# WiFi.net
KiCad netlist of a schematic drawn in Altium Designer
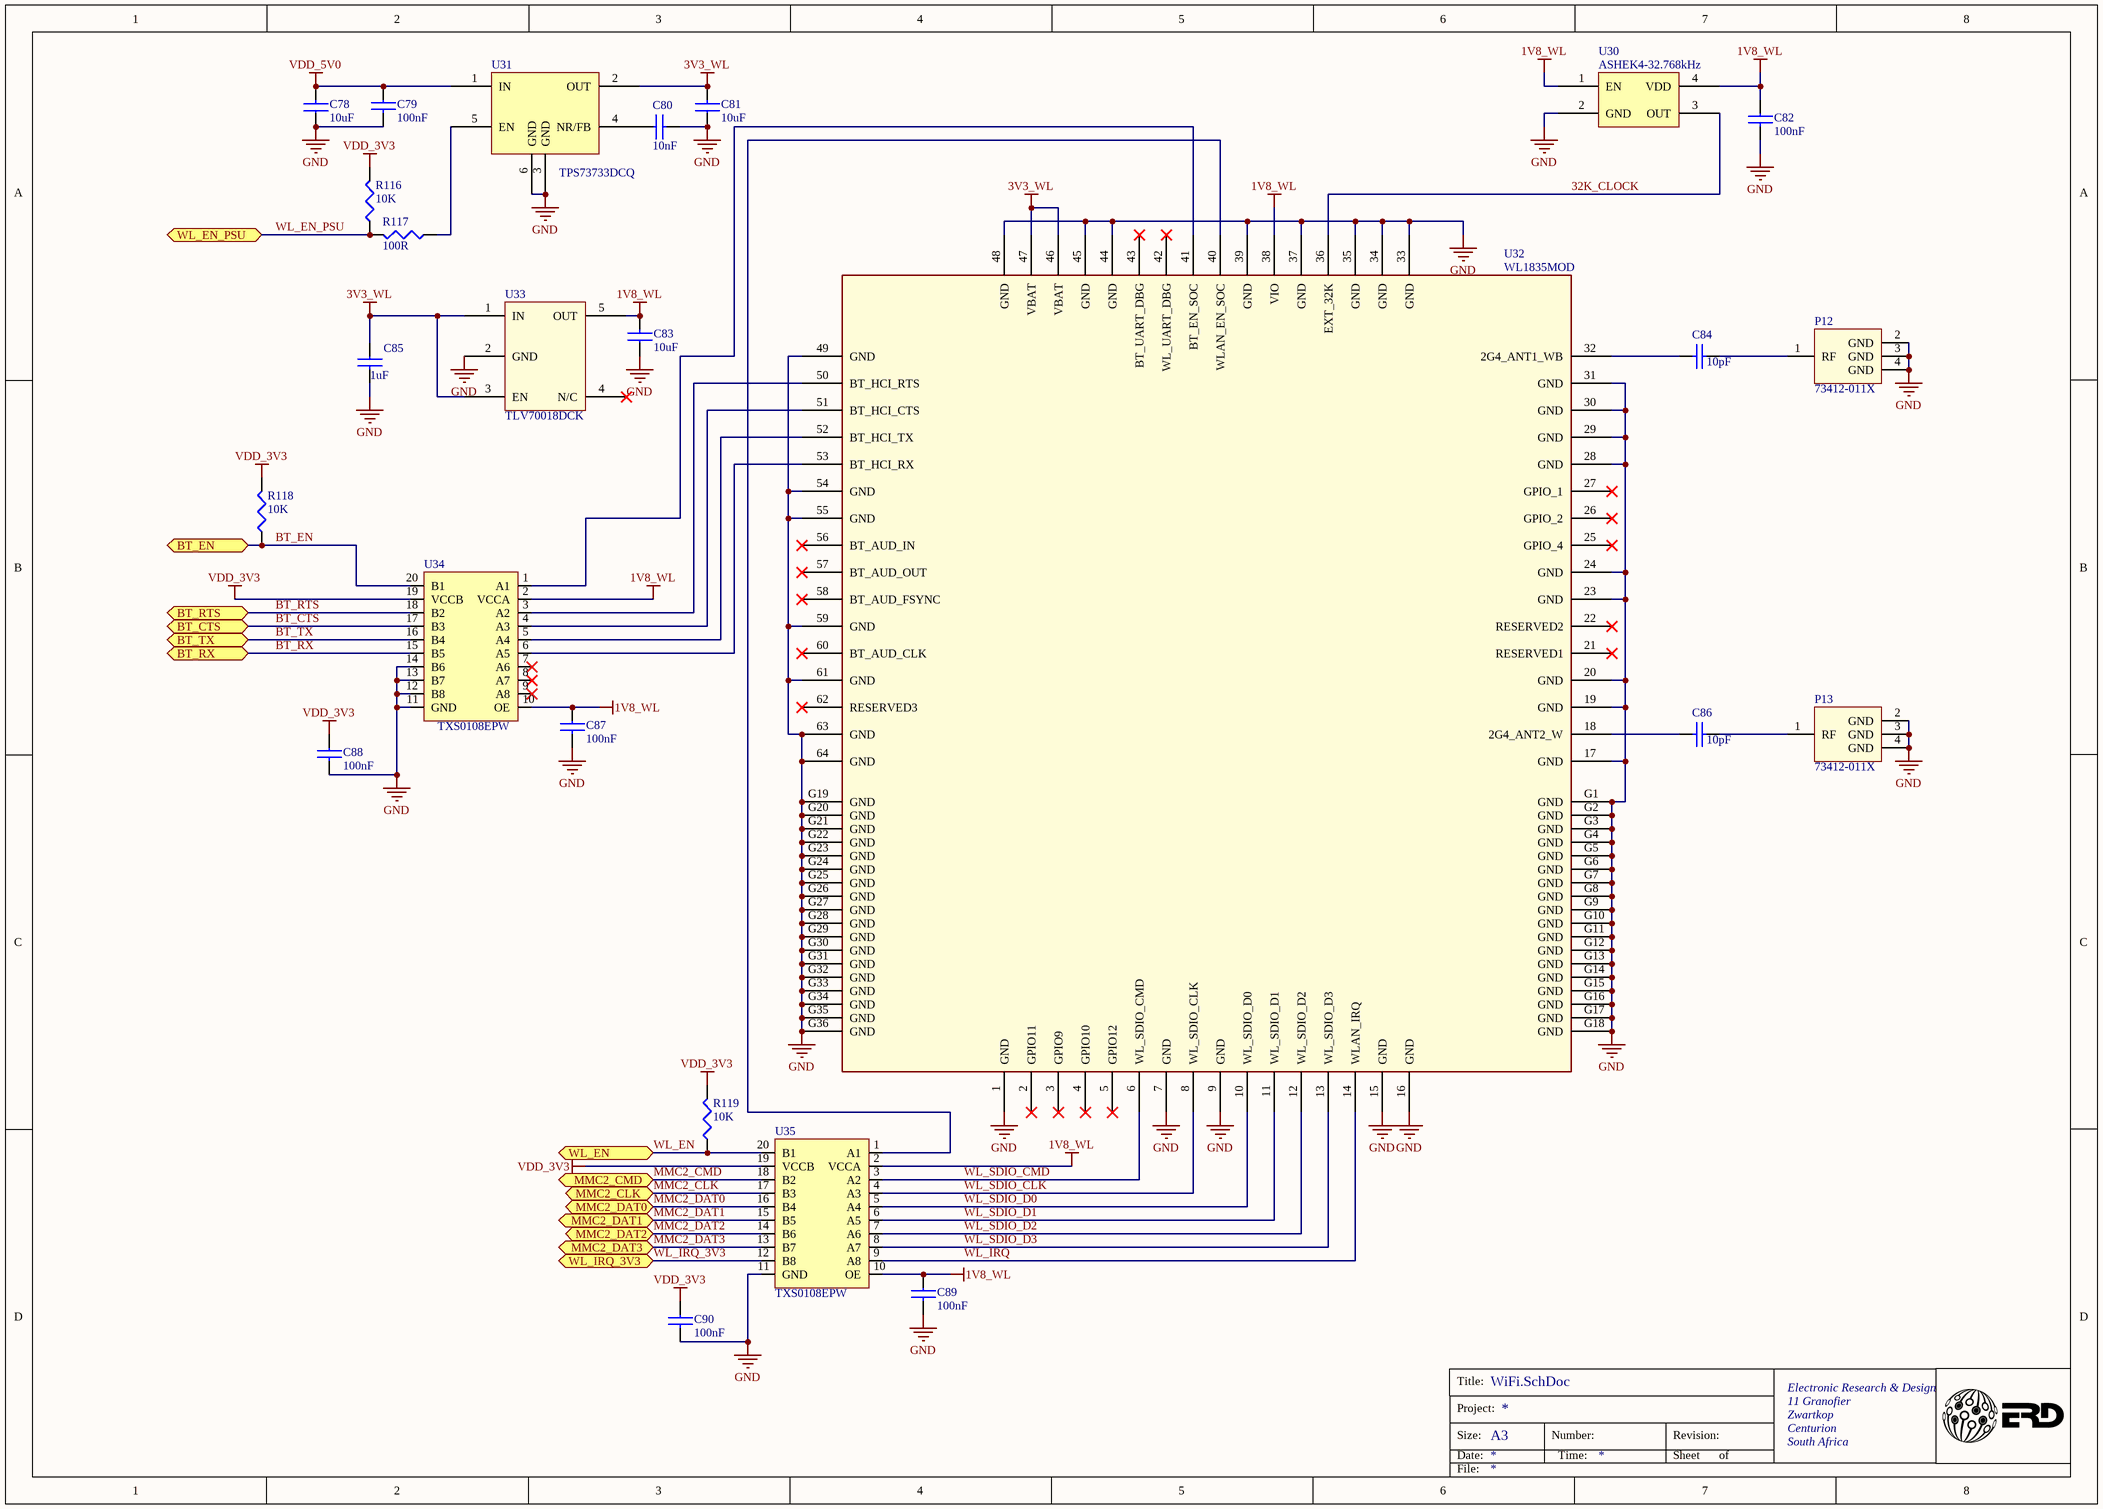
[diagram p0: WiFi.SchDoc]

(export (version "E")
  (design (tool "Eeschema 10.0.6"))
  (components
    (comp (ref "C78")
      (value "10uF")
      (footprint "CC0603")
      (description "CAP CER 10UF 25V 20% X5R 0603")
      (fields (field (name "MANUFACTURER") "Murata") (field (name "PARTNUMBER") "GRM188R61E106MA73D"))
      (libsource (lib "ERD TiAm") (part "CAP CER 0.1UF 10V 10% X5R 0402"))
    )
    (comp (ref "C79")
      (value "100nF")
      (footprint "CC0402")
      (description "CAP CER 0.1UF 50V 10% X7R 0402")
      (fields (field (name "MANUFACTURER") "Murata") (field (name "PARTNUMBER") "GCM155R71H104KE02D"))
      (libsource (lib "ERD TiAm") (part "CAP CER 0.1UF 10V 10% X5R 0402"))
    )
    (comp (ref "C80")
      (value "10nF")
      (footprint "CC0402")
      (description "CAP CER 10NF 50V 10% X7R 0402")
      (fields (field (name "MANUFACTURER") "Murata") (field (name "PART NUMBER") "GRM155R71H103KA88J"))
      (libsource (lib "ERD TiAm") (part "CAP CER 0.1UF 10V 10% X5R 0402"))
    )
    (comp (ref "C81")
      (value "10uF")
      (footprint "CC0603")
      (description "CAP CER 10UF 25V 20% X5R 0603")
      (fields (field (name "MANUFACTURER") "Murata") (field (name "PARTNUMBER") "GRM188R61E106MA73D"))
      (libsource (lib "ERD TiAm") (part "CAP CER 0.1UF 10V 10% X5R 0402"))
    )
    (comp (ref "C82")
      (value "100nF")
      (footprint "CC0402")
      (description "CAP CER 0.1UF 50V 10% X7R 0402")
      (fields (field (name "MANUFACTURER") "Murata") (field (name "PARTNUMBER") "GCM155R71H104KE02D"))
      (libsource (lib "ERD TiAm") (part "CAP CER 0.1UF 10V 10% X5R 0402"))
    )
    (comp (ref "C83")
      (value "10uF")
      (footprint "CC0603")
      (description "CAP CER 10UF 25V 20% X5R 0603")
      (fields (field (name "MANUFACTURER") "Murata") (field (name "PARTNUMBER") "GRM188R61E106MA73D"))
      (libsource (lib "ERD TiAm") (part "CAP CER 0.1UF 10V 10% X5R 0402"))
    )
    (comp (ref "C84")
      (value "10pF")
      (footprint "CC0402")
      (description "10pF/16V/X7R")
      (fields (field (name "TOLERANCE") "±20%") (field (name "VOLTAGE") "25V"))
      (libsource (lib "*") (part "CAPCERAMIC"))
    )
    (comp (ref "C85")
      (value "1uF")
      (footprint "CC0402")
      (description "CAP CER 1UF 10V 20% X5R 0402")
      (fields (field (name "MANUFACTURER") "Murata") (field (name "PART NUMBER") "GRM153R61A105ME95D"))
      (libsource (lib "ERD TiAm") (part "CAP CER 0.1UF 10V 10% X5R 0402"))
    )
    (comp (ref "C86")
      (value "10pF")
      (footprint "CC0402")
      (description "10pF/16V/X7R")
      (fields (field (name "TOLERANCE") "±20%") (field (name "VOLTAGE") "25V"))
      (libsource (lib "*") (part "CAPCERAMIC"))
    )
    (comp (ref "C87")
      (value "100nF")
      (footprint "CC0402")
      (description "CAP CER 0.1UF 50V 10% X7R 0402")
      (fields (field (name "MANUFACTURER") "Murata") (field (name "PARTNUMBER") "GCM155R71H104KE02D"))
      (libsource (lib "ERD TiAm") (part "CAP CER 0.1UF 10V 10% X5R 0402"))
    )
    (comp (ref "C88")
      (value "100nF")
      (footprint "CC0402")
      (description "CAP CER 0.1UF 50V 10% X7R 0402")
      (fields (field (name "MANUFACTURER") "Murata") (field (name "PARTNUMBER") "GCM155R71H104KE02D"))
      (libsource (lib "ERD TiAm") (part "CAP CER 0.1UF 10V 10% X5R 0402"))
    )
    (comp (ref "C89")
      (value "100nF")
      (footprint "CC0402")
      (description "CAP CER 0.1UF 50V 10% X7R 0402")
      (fields (field (name "MANUFACTURER") "Murata") (field (name "PARTNUMBER") "GCM155R71H104KE02D"))
      (libsource (lib "ERD TiAm") (part "CAP CER 0.1UF 10V 10% X5R 0402"))
    )
    (comp (ref "C90")
      (value "100nF")
      (footprint "CC0402")
      (description "CAP CER 0.1UF 50V 10% X7R 0402")
      (fields (field (name "MANUFACTURER") "Murata") (field (name "PARTNUMBER") "GCM155R71H104KE02D"))
      (libsource (lib "ERD TiAm") (part "CAP CER 0.1UF 10V 10% X5R 0402"))
    )
    (comp (ref "P12")
      (value "73412-011X")
      (footprint "73412-011X")
      (description "Molex U.FL SMD Receptacle")
      (libsource (lib "gADGET") (part "73412-011X"))
    )
    (comp (ref "P13")
      (value "73412-011X")
      (footprint "73412-011X")
      (description "Molex U.FL SMD Receptacle")
      (libsource (lib "gADGET") (part "73412-011X"))
    )
    (comp (ref "R116")
      (value "10K")
      (footprint "RC0402")
      (description "RES, 10K OHM, 1/16W, 1%, 0402")
      (fields (field (name "MANUFACTURER") "Yageo") (field (name "PART NUMBER") "RC0402FR-0710KL"))
      (libsource (lib "ERD TiAm") (part "RES_10K_1/16W_1%_0402"))
    )
    (comp (ref "R117")
      (value "100R")
      (footprint "RC0402")
      (description "RES, 100 OHM, 1/16W, 1%, 0402")
      (fields (field (name "MANUFACTURER") "Yageo") (field (name "PART NUMBER") "RC0402FR-07100RL"))
      (libsource (lib "ERD TiAm") (part "RES_10K_1/16W_1%_0402"))
    )
    (comp (ref "R118")
      (value "10K")
      (footprint "RC0402")
      (description "RES, 10K OHM, 1/16W, 1%, 0402")
      (fields (field (name "MANUFACTURER") "Yageo") (field (name "PART NUMBER") "RC0402FR-0710KL"))
      (libsource (lib "ERD TiAm") (part "RES_10K_1/16W_1%_0402"))
    )
    (comp (ref "R119")
      (value "10K")
      (footprint "RC0402")
      (description "RES, 10K OHM, 1/16W, 1%, 0402")
      (fields (field (name "MANUFACTURER") "Yageo") (field (name "PART NUMBER") "RC0402FR-0710KL"))
      (libsource (lib "ERD TiAm") (part "RES_10K_1/16W_1%_0402"))
    )
    (comp (ref "U30")
      (value "ASHEK4-32.768kHz")
      (footprint "SMD3.2X2.5")
      (description "32.768kHz SMD OSCILLATOR")
      (libsource (lib "SCH") (part "ASHEK4-32.768kHz"))
    )
    (comp (ref "U31")
      (value "TPS73733DCQ")
      (footprint "TPS73733DCQ")
      (libsource (lib "PoliceDemo") (part "TPS73733DCQ"))
    )
    (comp (ref "U32")
      (value "WL1835MOD")
      (footprint "E-13.4X13.3-N100_0.75-TOP")
      (libsource (lib "WL1835MODCOM8B_Library") (part "WG7835-T0B module_ref_130904"))
    )
    (comp (ref "U33")
      (value "TLV70018DCK")
      (footprint "SC-70-5")
      (description "200mA LOW DROPOUT REGULATOR")
      (libsource (lib "CameraModule") (part "TLV700"))
    )
    (comp (ref "U34")
      (value "TXS0108EPW")
      (footprint "TXB0108_PW_R")
      (libsource (lib "cc_SCH") (part "TXB0108PW"))
    )
    (comp (ref "U35")
      (value "TXS0108EPW")
      (footprint "TXB0108_PW_R")
      (libsource (lib "cc_SCH") (part "TXB0108PW"))
    )
  )
  (nets
    (net (code "1") (name "/32K_CLOCK") (class "Default")
      (node (ref "U30") (pin "3") (pinfunction "OUT_3") (pintype "passive"))
      (node (ref "U32") (pin "36") (pinfunction "EXT_32K_36") (pintype "passive"))
    )
    (net (code "2") (name "/BT_CTS") (class "Default")
      (node (ref "U34") (pin "17") (pinfunction "B3_17") (pintype "passive"))
    )
    (net (code "3") (name "/BT_EN") (class "Default")
      (node (ref "R118") (pin "1") (pinfunction "1_1") (pintype "passive"))
      (node (ref "U34") (pin "20") (pinfunction "B1_20") (pintype "passive"))
    )
    (net (code "4") (name "/BT_RTS") (class "Default")
      (node (ref "U34") (pin "18") (pinfunction "B2_18") (pintype "passive"))
    )
    (net (code "5") (name "/BT_RX") (class "Default")
      (node (ref "U34") (pin "15") (pinfunction "B5_15") (pintype "passive"))
    )
    (net (code "6") (name "/BT_TX") (class "Default")
      (node (ref "U34") (pin "16") (pinfunction "B4_16") (pintype "passive"))
    )
    (net (code "7") (name "/MMC2_CLK") (class "Default")
      (node (ref "U35") (pin "17") (pinfunction "B3_17") (pintype "passive"))
    )
    (net (code "8") (name "/MMC2_CMD") (class "Default")
      (node (ref "U35") (pin "18") (pinfunction "B2_18") (pintype "passive"))
    )
    (net (code "9") (name "/MMC2_DAT0") (class "Default")
      (node (ref "U35") (pin "16") (pinfunction "B4_16") (pintype "passive"))
    )
    (net (code "10") (name "/MMC2_DAT1") (class "Default")
      (node (ref "U35") (pin "15") (pinfunction "B5_15") (pintype "passive"))
    )
    (net (code "11") (name "/MMC2_DAT2") (class "Default")
      (node (ref "U35") (pin "14") (pinfunction "B6_14") (pintype "passive"))
    )
    (net (code "12") (name "/MMC2_DAT3") (class "Default")
      (node (ref "U35") (pin "13") (pinfunction "B7_13") (pintype "passive"))
    )
    (net (code "13") (name "/WL_EN") (class "Default")
      (node (ref "R119") (pin "1") (pinfunction "1_1") (pintype "passive"))
      (node (ref "U35") (pin "20") (pinfunction "B1_20") (pintype "passive"))
    )
    (net (code "14") (name "/WL_EN_PSU") (class "Default")
      (node (ref "R116") (pin "1") (pinfunction "1_1") (pintype "passive"))
      (node (ref "R117") (pin "2") (pinfunction "2_2") (pintype "passive"))
    )
    (net (code "15") (name "/WL_IRQ") (class "Default")
      (node (ref "U32") (pin "14") (pinfunction "WLAN_IRQ_14") (pintype "passive"))
      (node (ref "U35") (pin "9") (pinfunction "A8_9") (pintype "passive"))
    )
    (net (code "16") (name "/WL_IRQ_3V3") (class "Default")
      (node (ref "U35") (pin "12") (pinfunction "B8_12") (pintype "passive"))
    )
    (net (code "17") (name "/WL_SDIO_CLK") (class "Default")
      (node (ref "U32") (pin "8") (pinfunction "WL_SDIO_CLK_8") (pintype "passive"))
      (node (ref "U35") (pin "4") (pinfunction "A3_4") (pintype "passive"))
    )
    (net (code "18") (name "/WL_SDIO_CMD") (class "Default")
      (node (ref "U32") (pin "6") (pinfunction "WL_SDIO_CMD_6") (pintype "passive"))
      (node (ref "U35") (pin "3") (pinfunction "A2_3") (pintype "passive"))
    )
    (net (code "19") (name "/WL_SDIO_D0") (class "Default")
      (node (ref "U32") (pin "10") (pinfunction "WL_SDIO_D0_10") (pintype "passive"))
      (node (ref "U35") (pin "5") (pinfunction "A4_5") (pintype "passive"))
    )
    (net (code "20") (name "/WL_SDIO_D1") (class "Default")
      (node (ref "U32") (pin "11") (pinfunction "WL_SDIO_D1_11") (pintype "passive"))
      (node (ref "U35") (pin "6") (pinfunction "A5_6") (pintype "passive"))
    )
    (net (code "21") (name "/WL_SDIO_D2") (class "Default")
      (node (ref "U32") (pin "12") (pinfunction "WL_SDIO_D2_12") (pintype "passive"))
      (node (ref "U35") (pin "7") (pinfunction "A6_7") (pintype "passive"))
    )
    (net (code "22") (name "/WL_SDIO_D3") (class "Default")
      (node (ref "U32") (pin "13") (pinfunction "WL_SDIO_D3_13") (pintype "passive"))
      (node (ref "U35") (pin "8") (pinfunction "A7_8") (pintype "passive"))
    )
    (net (code "23") (name "1V8_WL") (class "Default")
      (node (ref "C82") (pin "1") (pinfunction "1_1") (pintype "passive"))
      (node (ref "C83") (pin "2") (pinfunction "2_2") (pintype "passive"))
      (node (ref "C87") (pin "1") (pinfunction "1_1") (pintype "passive"))
      (node (ref "C89") (pin "1") (pinfunction "1_1") (pintype "passive"))
      (node (ref "U30") (pin "1") (pinfunction "EN_1") (pintype "passive"))
      (node (ref "U30") (pin "4") (pinfunction "VDD_4") (pintype "passive"))
      (node (ref "U32") (pin "38") (pinfunction "VIO_38") (pintype "power_in"))
      (node (ref "U33") (pin "5") (pinfunction "OUT_5") (pintype "passive"))
      (node (ref "U34") (pin "10") (pinfunction "OE_10") (pintype "passive"))
      (node (ref "U34") (pin "2") (pinfunction "VCCA_2") (pintype "passive"))
      (node (ref "U35") (pin "10") (pinfunction "OE_10") (pintype "passive"))
      (node (ref "U35") (pin "2") (pinfunction "VCCA_2") (pintype "passive"))
    )
    (net (code "24") (name "3V3_WL") (class "Default")
      (node (ref "C81") (pin "2") (pinfunction "2_2") (pintype "passive"))
      (node (ref "C85") (pin "1") (pinfunction "1_1") (pintype "passive"))
      (node (ref "U31") (pin "2") (pinfunction "OUT_2") (pintype "passive"))
      (node (ref "U32") (pin "46") (pinfunction "VBAT_46") (pintype "power_in"))
      (node (ref "U32") (pin "47") (pinfunction "VBAT_47") (pintype "power_in"))
      (node (ref "U33") (pin "1") (pinfunction "IN_1") (pintype "passive"))
      (node (ref "U33") (pin "3") (pinfunction "EN_3") (pintype "passive"))
    )
    (net (code "25") (name "GND") (class "Default")
      (node (ref "C78") (pin "1") (pinfunction "1_1") (pintype "passive"))
      (node (ref "C79") (pin "2") (pinfunction "2_2") (pintype "passive"))
      (node (ref "C80") (pin "2") (pinfunction "2_2") (pintype "passive"))
      (node (ref "C81") (pin "1") (pinfunction "1_1") (pintype "passive"))
      (node (ref "C82") (pin "2") (pinfunction "2_2") (pintype "passive"))
      (node (ref "C83") (pin "1") (pinfunction "1_1") (pintype "passive"))
      (node (ref "C85") (pin "2") (pinfunction "2_2") (pintype "passive"))
      (node (ref "C87") (pin "2") (pinfunction "2_2") (pintype "passive"))
      (node (ref "C88") (pin "2") (pinfunction "2_2") (pintype "passive"))
      (node (ref "C89") (pin "2") (pinfunction "2_2") (pintype "passive"))
      (node (ref "C90") (pin "2") (pinfunction "2_2") (pintype "passive"))
      (node (ref "P12") (pin "2") (pinfunction "GND_2") (pintype "passive"))
      (node (ref "P12") (pin "3") (pinfunction "GND_3") (pintype "passive"))
      (node (ref "P12") (pin "4") (pinfunction "GND_4") (pintype "passive"))
      (node (ref "P13") (pin "2") (pinfunction "GND_2") (pintype "passive"))
      (node (ref "P13") (pin "3") (pinfunction "GND_3") (pintype "passive"))
      (node (ref "P13") (pin "4") (pinfunction "GND_4") (pintype "passive"))
      (node (ref "U30") (pin "2") (pinfunction "GND_2") (pintype "passive"))
      (node (ref "U31") (pin "3") (pinfunction "GND_3") (pintype "passive"))
      (node (ref "U31") (pin "6") (pinfunction "GND_6") (pintype "passive"))
      (node (ref "U32") (pin "1") (pinfunction "GND_1") (pintype "power_in"))
      (node (ref "U32") (pin "15") (pinfunction "GND_15") (pintype "power_in"))
      (node (ref "U32") (pin "16") (pinfunction "GND_16") (pintype "power_in"))
      (node (ref "U32") (pin "17") (pinfunction "GND_17") (pintype "power_in"))
      (node (ref "U32") (pin "19") (pinfunction "GND_19") (pintype "power_in"))
      (node (ref "U32") (pin "20") (pinfunction "GND_20") (pintype "power_in"))
      (node (ref "U32") (pin "23") (pinfunction "GND_23") (pintype "power_in"))
      (node (ref "U32") (pin "24") (pinfunction "GND_24") (pintype "power_in"))
      (node (ref "U32") (pin "28") (pinfunction "GND_28") (pintype "power_in"))
      (node (ref "U32") (pin "29") (pinfunction "GND_29") (pintype "power_in"))
      (node (ref "U32") (pin "30") (pinfunction "GND_30") (pintype "power_in"))
      (node (ref "U32") (pin "31") (pinfunction "GND_31") (pintype "power_in"))
      (node (ref "U32") (pin "33") (pinfunction "GND_33") (pintype "power_in"))
      (node (ref "U32") (pin "34") (pinfunction "GND_34") (pintype "power_in"))
      (node (ref "U32") (pin "35") (pinfunction "GND_35") (pintype "power_in"))
      (node (ref "U32") (pin "37") (pinfunction "GND_37") (pintype "power_in"))
      (node (ref "U32") (pin "39") (pinfunction "GND_39") (pintype "power_in"))
      (node (ref "U32") (pin "44") (pinfunction "GND_44") (pintype "power_in"))
      (node (ref "U32") (pin "45") (pinfunction "GND_45") (pintype "power_in"))
      (node (ref "U32") (pin "48") (pinfunction "GND_48") (pintype "power_in"))
      (node (ref "U32") (pin "49") (pinfunction "GND_49") (pintype "power_in"))
      (node (ref "U32") (pin "54") (pinfunction "GND_54") (pintype "power_in"))
      (node (ref "U32") (pin "55") (pinfunction "GND_55") (pintype "power_in"))
      (node (ref "U32") (pin "59") (pinfunction "GND_59") (pintype "power_in"))
      (node (ref "U32") (pin "61") (pinfunction "GND_61") (pintype "power_in"))
      (node (ref "U32") (pin "63") (pinfunction "GND_63") (pintype "power_in"))
      (node (ref "U32") (pin "64") (pinfunction "GND_64") (pintype "power_in"))
      (node (ref "U32") (pin "7") (pinfunction "GND_7") (pintype "power_in"))
      (node (ref "U32") (pin "9") (pinfunction "GND_9") (pintype "power_in"))
      (node (ref "U32") (pin "G1") (pinfunction "GND_G1") (pintype "power_in"))
      (node (ref "U32") (pin "G10") (pinfunction "GND_G10") (pintype "power_in"))
      (node (ref "U32") (pin "G11") (pinfunction "GND_G11") (pintype "power_in"))
      (node (ref "U32") (pin "G12") (pinfunction "GND_G12") (pintype "power_in"))
      (node (ref "U32") (pin "G13") (pinfunction "GND_G13") (pintype "power_in"))
      (node (ref "U32") (pin "G14") (pinfunction "GND_G14") (pintype "power_in"))
      (node (ref "U32") (pin "G15") (pinfunction "GND_G15") (pintype "power_in"))
      (node (ref "U32") (pin "G16") (pinfunction "GND_G16") (pintype "power_in"))
      (node (ref "U32") (pin "G17") (pinfunction "GND_G17") (pintype "power_in"))
      (node (ref "U32") (pin "G18") (pinfunction "GND_G18") (pintype "power_in"))
      (node (ref "U32") (pin "G19") (pinfunction "GND_G19") (pintype "power_in"))
      (node (ref "U32") (pin "G2") (pinfunction "GND_G2") (pintype "power_in"))
      (node (ref "U32") (pin "G20") (pinfunction "GND_G20") (pintype "power_in"))
      (node (ref "U32") (pin "G21") (pinfunction "GND_G21") (pintype "power_in"))
      (node (ref "U32") (pin "G22") (pinfunction "GND_G22") (pintype "power_in"))
      (node (ref "U32") (pin "G23") (pinfunction "GND_G23") (pintype "power_in"))
      (node (ref "U32") (pin "G24") (pinfunction "GND_G24") (pintype "power_in"))
      (node (ref "U32") (pin "G25") (pinfunction "GND_G25") (pintype "power_in"))
      (node (ref "U32") (pin "G26") (pinfunction "GND_G26") (pintype "power_in"))
      (node (ref "U32") (pin "G27") (pinfunction "GND_G27") (pintype "power_in"))
      (node (ref "U32") (pin "G28") (pinfunction "GND_G28") (pintype "power_in"))
      (node (ref "U32") (pin "G29") (pinfunction "GND_G29") (pintype "power_in"))
      (node (ref "U32") (pin "G3") (pinfunction "GND_G3") (pintype "power_in"))
      (node (ref "U32") (pin "G30") (pinfunction "GND_G30") (pintype "power_in"))
      (node (ref "U32") (pin "G31") (pinfunction "GND_G31") (pintype "power_in"))
      (node (ref "U32") (pin "G32") (pinfunction "GND_G32") (pintype "power_in"))
      (node (ref "U32") (pin "G33") (pinfunction "GND_G33") (pintype "power_in"))
      (node (ref "U32") (pin "G34") (pinfunction "GND_G34") (pintype "power_in"))
      (node (ref "U32") (pin "G35") (pinfunction "GND_G35") (pintype "power_in"))
      (node (ref "U32") (pin "G36") (pinfunction "GND_G36") (pintype "power_in"))
      (node (ref "U32") (pin "G4") (pinfunction "GND_G4") (pintype "power_in"))
      (node (ref "U32") (pin "G5") (pinfunction "GND_G5") (pintype "power_in"))
      (node (ref "U32") (pin "G6") (pinfunction "GND_G6") (pintype "power_in"))
      (node (ref "U32") (pin "G7") (pinfunction "GND_G7") (pintype "power_in"))
      (node (ref "U32") (pin "G8") (pinfunction "GND_G8") (pintype "power_in"))
      (node (ref "U32") (pin "G9") (pinfunction "GND_G9") (pintype "power_in"))
      (node (ref "U33") (pin "2") (pinfunction "GND_2") (pintype "passive"))
      (node (ref "U34") (pin "11") (pinfunction "GND_11") (pintype "passive"))
      (node (ref "U34") (pin "12") (pinfunction "B8_12") (pintype "passive"))
      (node (ref "U34") (pin "13") (pinfunction "B7_13") (pintype "passive"))
      (node (ref "U34") (pin "14") (pinfunction "B6_14") (pintype "passive"))
      (node (ref "U35") (pin "11") (pinfunction "GND_11") (pintype "passive"))
    )
    (net (code "26") (name "Net-(P12-RF)") (class "Default")
      (node (ref "C84") (pin "1") (pintype "passive"))
      (node (ref "P12") (pin "1") (pinfunction "RF_1") (pintype "passive"))
    )
    (net (code "27") (name "Net-(P13-RF)") (class "Default")
      (node (ref "C86") (pin "1") (pintype "passive"))
      (node (ref "P13") (pin "1") (pinfunction "RF_1") (pintype "passive"))
    )
    (net (code "28") (name "Net-(U31-EN)") (class "Default")
      (node (ref "R117") (pin "1") (pinfunction "1_1") (pintype "passive"))
      (node (ref "U31") (pin "5") (pinfunction "EN_5") (pintype "passive"))
    )
    (net (code "29") (name "Net-(U31-NR{slash}FB)") (class "Default")
      (node (ref "C80") (pin "1") (pinfunction "1_1") (pintype "passive"))
      (node (ref "U31") (pin "4") (pinfunction "NR/FB_4") (pintype "passive"))
    )
    (net (code "30") (name "Net-(U32-2G4_ANT1_WB)") (class "Default")
      (node (ref "C84") (pin "2") (pintype "passive"))
      (node (ref "U32") (pin "32") (pinfunction "2G4_ANT1_WB_32") (pintype "passive"))
    )
    (net (code "31") (name "Net-(U32-2G4_ANT2_W)") (class "Default")
      (node (ref "C86") (pin "2") (pintype "passive"))
      (node (ref "U32") (pin "18") (pinfunction "2G4_ANT2_W_18") (pintype "passive"))
    )
    (net (code "32") (name "Net-(U32-BT_EN_SOC)") (class "Default")
      (node (ref "U32") (pin "41") (pinfunction "BT_EN_SOC_41") (pintype "passive"))
      (node (ref "U34") (pin "1") (pinfunction "A1_1") (pintype "passive"))
    )
    (net (code "33") (name "Net-(U32-BT_HCI_CTS)") (class "Default")
      (node (ref "U32") (pin "51") (pinfunction "BT_HCI_CTS_51") (pintype "passive"))
      (node (ref "U34") (pin "4") (pinfunction "A3_4") (pintype "passive"))
    )
    (net (code "34") (name "Net-(U32-BT_HCI_RTS)") (class "Default")
      (node (ref "U32") (pin "50") (pinfunction "BT_HCI_RTS_50") (pintype "passive"))
      (node (ref "U34") (pin "3") (pinfunction "A2_3") (pintype "passive"))
    )
    (net (code "35") (name "Net-(U32-BT_HCI_RX)") (class "Default")
      (node (ref "U32") (pin "53") (pinfunction "BT_HCI_RX_53") (pintype "passive"))
      (node (ref "U34") (pin "6") (pinfunction "A5_6") (pintype "passive"))
    )
    (net (code "36") (name "Net-(U32-BT_HCI_TX)") (class "Default")
      (node (ref "U32") (pin "52") (pinfunction "BT_HCI_TX_52") (pintype "passive"))
      (node (ref "U34") (pin "5") (pinfunction "A4_5") (pintype "passive"))
    )
    (net (code "37") (name "Net-(U32-WLAN_EN_SOC)") (class "Default")
      (node (ref "U32") (pin "40") (pinfunction "WLAN_EN_SOC_40") (pintype "passive"))
      (node (ref "U35") (pin "1") (pinfunction "A1_1") (pintype "passive"))
    )
    (net (code "38") (name "VDD_3V3") (class "Default")
      (node (ref "C88") (pin "1") (pinfunction "1_1") (pintype "passive"))
      (node (ref "C90") (pin "1") (pinfunction "1_1") (pintype "passive"))
      (node (ref "R116") (pin "2") (pinfunction "2_2") (pintype "passive"))
      (node (ref "R118") (pin "2") (pinfunction "2_2") (pintype "passive"))
      (node (ref "R119") (pin "2") (pinfunction "2_2") (pintype "passive"))
      (node (ref "U34") (pin "19") (pinfunction "VCCB_19") (pintype "passive"))
      (node (ref "U35") (pin "19") (pinfunction "VCCB_19") (pintype "passive"))
    )
    (net (code "39") (name "VDD_5V0") (class "Default")
      (node (ref "C78") (pin "2") (pinfunction "2_2") (pintype "passive"))
      (node (ref "C79") (pin "1") (pinfunction "1_1") (pintype "passive"))
      (node (ref "U31") (pin "1") (pinfunction "IN_1") (pintype "passive"))
    )
    (net (code "40") (name "unconnected-(U32-BT_AUD_CLK-Pad60)") (class "Default")
      (node (ref "U32") (pin "60") (pinfunction "BT_AUD_CLK_60") (pintype "passive+no_connect"))
    )
    (net (code "41") (name "unconnected-(U32-BT_AUD_FSYNC-Pad58)") (class "Default")
      (node (ref "U32") (pin "58") (pinfunction "BT_AUD_FSYNC_58") (pintype "passive+no_connect"))
    )
    (net (code "42") (name "unconnected-(U32-BT_AUD_IN-Pad56)") (class "Default")
      (node (ref "U32") (pin "56") (pinfunction "BT_AUD_IN_56") (pintype "passive+no_connect"))
    )
    (net (code "43") (name "unconnected-(U32-BT_AUD_OUT-Pad57)") (class "Default")
      (node (ref "U32") (pin "57") (pinfunction "BT_AUD_OUT_57") (pintype "passive+no_connect"))
    )
    (net (code "44") (name "unconnected-(U32-BT_UART_DBG-Pad43)") (class "Default")
      (node (ref "U32") (pin "43") (pinfunction "BT_UART_DBG_43") (pintype "passive+no_connect"))
    )
    (net (code "45") (name "unconnected-(U32-GPIO9-Pad3)") (class "Default")
      (node (ref "U32") (pin "3") (pinfunction "GPIO9_3") (pintype "passive+no_connect"))
    )
    (net (code "46") (name "unconnected-(U32-GPIO10-Pad4)") (class "Default")
      (node (ref "U32") (pin "4") (pinfunction "GPIO10_4") (pintype "passive+no_connect"))
    )
    (net (code "47") (name "unconnected-(U32-GPIO11-Pad2)") (class "Default")
      (node (ref "U32") (pin "2") (pinfunction "GPIO11_2") (pintype "passive+no_connect"))
    )
    (net (code "48") (name "unconnected-(U32-GPIO12-Pad5)") (class "Default")
      (node (ref "U32") (pin "5") (pinfunction "GPIO12_5") (pintype "passive+no_connect"))
    )
    (net (code "49") (name "unconnected-(U32-GPIO_1-Pad27)") (class "Default")
      (node (ref "U32") (pin "27") (pinfunction "GPIO_1_27") (pintype "passive+no_connect"))
    )
    (net (code "50") (name "unconnected-(U32-GPIO_2-Pad26)") (class "Default")
      (node (ref "U32") (pin "26") (pinfunction "GPIO_2_26") (pintype "passive+no_connect"))
    )
    (net (code "51") (name "unconnected-(U32-GPIO_4-Pad25)") (class "Default")
      (node (ref "U32") (pin "25") (pinfunction "GPIO_4_25") (pintype "passive+no_connect"))
    )
    (net (code "52") (name "unconnected-(U32-RESERVED1-Pad21)") (class "Default")
      (node (ref "U32") (pin "21") (pinfunction "RESERVED1_21") (pintype "passive+no_connect"))
    )
    (net (code "53") (name "unconnected-(U32-RESERVED2-Pad22)") (class "Default")
      (node (ref "U32") (pin "22") (pinfunction "RESERVED2_22") (pintype "passive+no_connect"))
    )
    (net (code "54") (name "unconnected-(U32-RESERVED3-Pad62)") (class "Default")
      (node (ref "U32") (pin "62") (pinfunction "RESERVED3_62") (pintype "passive+no_connect"))
    )
    (net (code "55") (name "unconnected-(U32-WL_UART_DBG-Pad42)") (class "Default")
      (node (ref "U32") (pin "42") (pinfunction "WL_UART_DBG_42") (pintype "passive+no_connect"))
    )
    (net (code "56") (name "unconnected-(U33-N{slash}C-Pad4)") (class "Default")
      (node (ref "U33") (pin "4") (pinfunction "N/C_4") (pintype "passive+no_connect"))
    )
    (net (code "57") (name "unconnected-(U34-A6-Pad7)") (class "Default")
      (node (ref "U34") (pin "7") (pinfunction "A6_7") (pintype "passive+no_connect"))
    )
    (net (code "58") (name "unconnected-(U34-A7-Pad8)") (class "Default")
      (node (ref "U34") (pin "8") (pinfunction "A7_8") (pintype "passive+no_connect"))
    )
    (net (code "59") (name "unconnected-(U34-A8-Pad9)") (class "Default")
      (node (ref "U34") (pin "9") (pinfunction "A8_9") (pintype "passive+no_connect"))
    )
  )
)
